# PCB-DISP128x32.net
KiCad netlist of a schematic drawn in EAGLE
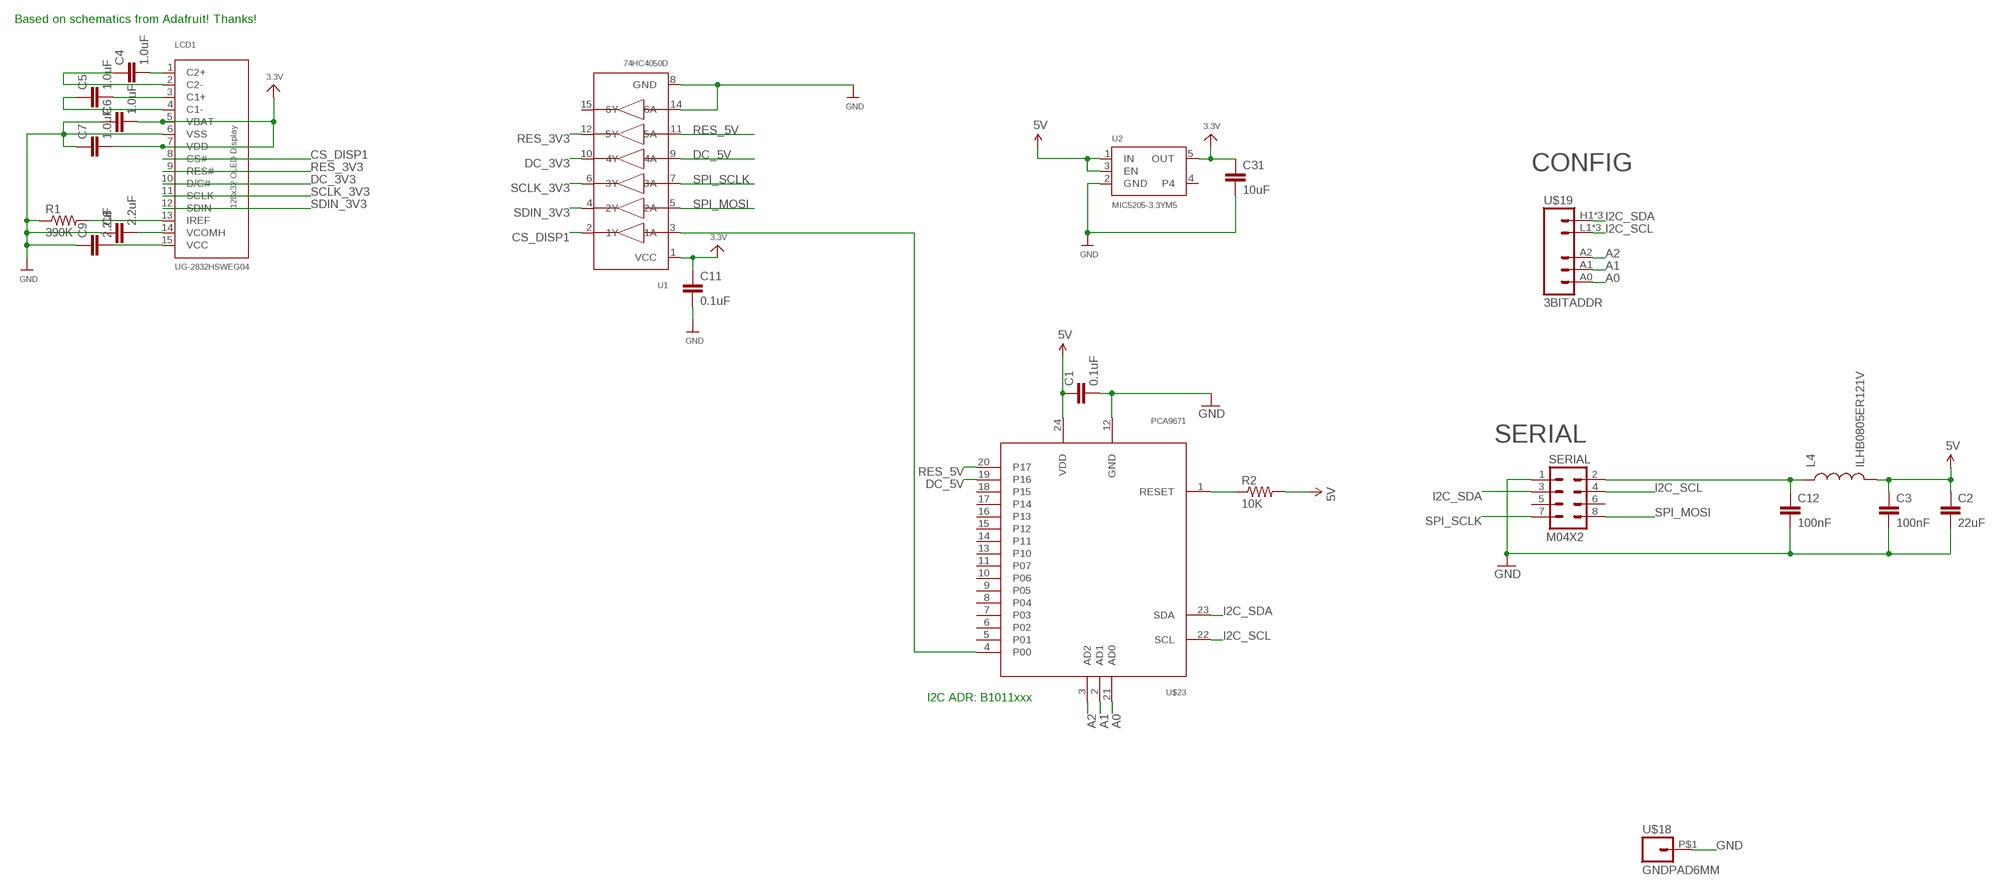
[diagram p0: schematic, sheet 1]

(export (version "E")
  (design (tool "Eeschema 10.0.6"))
  (components
    (comp (ref "C1")
      (value "0.1uF")
      (footprint "eagle-import:0603-CAP")
      (libsource (lib "eagle-import") (part "CAP0603-CAP"))
    )
    (comp (ref "C2")
      (value "22uF")
      (footprint "eagle-import:0805")
      (libsource (lib "eagle-import") (part "CAP0805"))
    )
    (comp (ref "C3")
      (value "100nF")
      (footprint "eagle-import:0603-CAP")
      (libsource (lib "eagle-import") (part "CAP0603-CAP"))
    )
    (comp (ref "C4")
      (value "1.0uF")
      (footprint "eagle-import:0603-CAP")
      (libsource (lib "eagle-import") (part "CAP0603-CAP"))
    )
    (comp (ref "C5")
      (value "1.0uF")
      (footprint "eagle-import:0603-CAP")
      (libsource (lib "eagle-import") (part "CAP0603-CAP"))
    )
    (comp (ref "C6")
      (value "1.0uF")
      (footprint "eagle-import:0603-CAP")
      (libsource (lib "eagle-import") (part "CAP0603-CAP"))
    )
    (comp (ref "C7")
      (value "1.0uF")
      (footprint "eagle-import:0603-CAP")
      (libsource (lib "eagle-import") (part "CAP0603-CAP"))
    )
    (comp (ref "C8")
      (value "2.2uF")
      (footprint "eagle-import:0603-CAP")
      (libsource (lib "eagle-import") (part "CAP0603-CAP"))
    )
    (comp (ref "C9")
      (value "2.2uF")
      (footprint "eagle-import:0603-CAP")
      (libsource (lib "eagle-import") (part "CAP0603-CAP"))
    )
    (comp (ref "C11")
      (value "0.1uF")
      (footprint "eagle-import:0603-CAP")
      (libsource (lib "eagle-import") (part "CAP0603-CAP"))
    )
    (comp (ref "C12")
      (value "100nF")
      (footprint "eagle-import:0603-CAP")
      (libsource (lib "eagle-import") (part "CAP0603-CAP"))
    )
    (comp (ref "C31")
      (value "10uF")
      (footprint "eagle-import:0805")
      (libsource (lib "eagle-import") (part "CAP0805"))
    )
    (comp (ref "L4")
      (value "ILHB0805ER121V")
      (footprint "eagle-import:0805")
      (libsource (lib "eagle-import") (part "INDUCTOR0805"))
    )
    (comp (ref "LCD1")
      (value "UG-2832HSWEG04")
      (footprint "eagle-import:UG-2832HSWEG04_WRAPAROUND")
      (libsource (lib "eagle-import") (part "OLED_UG-2832HSWEG04WRAPAROUND"))
    )
    (comp (ref "R1")
      (value "390K")
      (footprint "eagle-import:0603-RES")
      (libsource (lib "eagle-import") (part "RESISTOR0603-RES"))
    )
    (comp (ref "R2")
      (value "10K")
      (footprint "eagle-import:0603-RES")
      (libsource (lib "eagle-import") (part "RESISTOR0603-RES"))
    )
    (comp (ref "SERIAL")
      (value "M04X2")
      (footprint "eagle-import:2X4")
      (libsource (lib "eagle-import") (part "M04X2"))
    )
    (comp (ref "U$18")
      (value "GNDPAD6MM")
      (footprint "eagle-import:3.2MMPAD6MM")
      (libsource (lib "eagle-import") (part "GNDPAD6MM"))
    )
    (comp (ref "U$19")
      (value "3BITADDR")
      (footprint "eagle-import:3BITADDR")
      (libsource (lib "eagle-import") (part "3BITADDR"))
    )
    (comp (ref "U$23")
      (value "PCA9671")
      (footprint "eagle-import:TSSOP24")
      (libsource (lib "eagle-import") (part "PCA9671"))
    )
    (comp (ref "U1")
      (value "74HC4050D")
      (footprint "eagle-import:TSSOP16")
      (libsource (lib "eagle-import") (part "74HC4050DTSSOP16"))
    )
    (comp (ref "U2")
      (value "MIC5205-3.3YM5")
      (footprint "eagle-import:SOT23-5")
      (libsource (lib "eagle-import") (part "VREG_SOT23-5"))
    )
  )
  (nets
    (net (code "1") (name "3.3V") (class "Default")
      (node (ref "C11") (pin "1") (pinfunction "1_1") (pintype "passive"))
      (node (ref "C31") (pin "1") (pinfunction "1_1") (pintype "passive"))
      (node (ref "C6") (pin "2") (pinfunction "2_2") (pintype "passive"))
      (node (ref "C7") (pin "2") (pinfunction "2_2") (pintype "passive"))
      (node (ref "LCD1") (pin "5") (pinfunction "VBAT_5") (pintype "bidirectional"))
      (node (ref "LCD1") (pin "7") (pinfunction "VDD_7") (pintype "bidirectional"))
      (node (ref "U1") (pin "1") (pinfunction "VCC_1") (pintype "bidirectional"))
      (node (ref "U2") (pin "5") (pinfunction "OUT_5") (pintype "bidirectional"))
    )
    (net (code "2") (name "5V") (class "Default")
      (node (ref "C1") (pin "1") (pinfunction "1_1") (pintype "passive"))
      (node (ref "C2") (pin "1") (pinfunction "1_1") (pintype "passive"))
      (node (ref "C3") (pin "1") (pinfunction "1_1") (pintype "passive"))
      (node (ref "L4") (pin "2") (pinfunction "2_2") (pintype "passive"))
      (node (ref "R2") (pin "2") (pinfunction "2_2") (pintype "passive"))
      (node (ref "U$23") (pin "24") (pinfunction "VDD_24") (pintype "power_in"))
      (node (ref "U2") (pin "1") (pinfunction "IN_1") (pintype "bidirectional"))
      (node (ref "U2") (pin "3") (pinfunction "EN_3") (pintype "bidirectional"))
    )
    (net (code "3") (name "A0") (class "Default")
      (node (ref "U$19") (pin "A0") (pinfunction "A0_A0") (pintype "passive"))
      (node (ref "U$23") (pin "21") (pinfunction "AD0_21") (pintype "input"))
    )
    (net (code "4") (name "A1") (class "Default")
      (node (ref "U$19") (pin "A1") (pinfunction "A1_A1") (pintype "passive"))
      (node (ref "U$23") (pin "2") (pinfunction "AD1_2") (pintype "input"))
    )
    (net (code "5") (name "A2") (class "Default")
      (node (ref "U$19") (pin "A2") (pinfunction "A2_A2") (pintype "passive"))
      (node (ref "U$23") (pin "3") (pinfunction "AD2_3") (pintype "input"))
    )
    (net (code "6") (name "CS_DISP1") (class "Default")
      (node (ref "LCD1") (pin "8") (pinfunction "CS#_8") (pintype "bidirectional"))
      (node (ref "U1") (pin "2") (pinfunction "1Y_2") (pintype "bidirectional"))
    )
    (net (code "7") (name "DC_3V3") (class "Default")
      (node (ref "LCD1") (pin "10") (pinfunction "D/C#_10") (pintype "bidirectional"))
      (node (ref "U1") (pin "10") (pinfunction "4Y_10") (pintype "bidirectional"))
    )
    (net (code "8") (name "DC_5V") (class "Default")
      (node (ref "U$23") (pin "19") (pinfunction "P16_19") (pintype "output"))
      (node (ref "U1") (pin "9") (pinfunction "4A_9") (pintype "bidirectional"))
    )
    (net (code "9") (name "GND") (class "Default")
      (node (ref "C1") (pin "2") (pinfunction "2_2") (pintype "passive"))
      (node (ref "C11") (pin "2") (pinfunction "2_2") (pintype "passive"))
      (node (ref "C12") (pin "2") (pinfunction "2_2") (pintype "passive"))
      (node (ref "C2") (pin "2") (pinfunction "2_2") (pintype "passive"))
      (node (ref "C3") (pin "2") (pinfunction "2_2") (pintype "passive"))
      (node (ref "C31") (pin "2") (pinfunction "2_2") (pintype "passive"))
      (node (ref "C6") (pin "1") (pinfunction "1_1") (pintype "passive"))
      (node (ref "C7") (pin "1") (pinfunction "1_1") (pintype "passive"))
      (node (ref "C8") (pin "1") (pinfunction "1_1") (pintype "passive"))
      (node (ref "C9") (pin "1") (pinfunction "1_1") (pintype "passive"))
      (node (ref "LCD1") (pin "6") (pinfunction "VSS_6") (pintype "bidirectional"))
      (node (ref "R1") (pin "1") (pinfunction "1_1") (pintype "passive"))
      (node (ref "SERIAL") (pin "1") (pinfunction "1_1") (pintype "passive"))
      (node (ref "U$18") (pin "P$1") (pinfunction "1_P$1") (pintype "passive"))
      (node (ref "U$23") (pin "12") (pinfunction "GND_12") (pintype "power_in"))
      (node (ref "U1") (pin "14") (pinfunction "6A_14") (pintype "bidirectional"))
      (node (ref "U1") (pin "8") (pinfunction "GND_8") (pintype "bidirectional"))
      (node (ref "U2") (pin "2") (pinfunction "GND_2") (pintype "bidirectional"))
    )
    (net (code "10") (name "I2C_SCL") (class "Default")
      (node (ref "SERIAL") (pin "4") (pinfunction "4_4") (pintype "passive"))
      (node (ref "U$19") (pin "L1") (pinfunction "GND_L1") (pintype "passive"))
      (node (ref "U$19") (pin "L2") (pinfunction "GND_L2") (pintype "passive"))
      (node (ref "U$19") (pin "L3") (pinfunction "GND_L3") (pintype "passive"))
      (node (ref "U$23") (pin "22") (pinfunction "SCL_22") (pintype "input"))
    )
    (net (code "11") (name "I2C_SDA") (class "Default")
      (node (ref "SERIAL") (pin "3") (pinfunction "3_3") (pintype "passive"))
      (node (ref "U$19") (pin "H1") (pinfunction "VCC_H1") (pintype "passive"))
      (node (ref "U$19") (pin "H2") (pinfunction "VCC_H2") (pintype "passive"))
      (node (ref "U$19") (pin "H3") (pinfunction "VCC_H3") (pintype "passive"))
      (node (ref "U$23") (pin "23") (pinfunction "SDA_23") (pintype "input"))
    )
    (net (code "12") (name "Net-(C12-Pad1)") (class "Default")
      (node (ref "C12") (pin "1") (pinfunction "1_1") (pintype "passive"))
      (node (ref "L4") (pin "1") (pinfunction "1_1") (pintype "passive"))
      (node (ref "SERIAL") (pin "2") (pinfunction "2_2") (pintype "passive"))
    )
    (net (code "13") (name "Net-(LCD1-C1+)") (class "Default")
      (node (ref "C5") (pin "2") (pinfunction "2_2") (pintype "passive"))
      (node (ref "LCD1") (pin "3") (pinfunction "C1+_3") (pintype "bidirectional"))
    )
    (net (code "14") (name "Net-(LCD1-C1-)") (class "Default")
      (node (ref "C5") (pin "1") (pinfunction "1_1") (pintype "passive"))
      (node (ref "LCD1") (pin "4") (pinfunction "C1-_4") (pintype "bidirectional"))
    )
    (net (code "15") (name "Net-(LCD1-C2+)") (class "Default")
      (node (ref "C4") (pin "2") (pinfunction "2_2") (pintype "passive"))
      (node (ref "LCD1") (pin "1") (pinfunction "C2+_1") (pintype "bidirectional"))
    )
    (net (code "16") (name "Net-(LCD1-C2-)") (class "Default")
      (node (ref "C4") (pin "1") (pinfunction "1_1") (pintype "passive"))
      (node (ref "LCD1") (pin "2") (pinfunction "C2-_2") (pintype "bidirectional"))
    )
    (net (code "17") (name "Net-(LCD1-IREF)") (class "Default")
      (node (ref "LCD1") (pin "13") (pinfunction "IREF_13") (pintype "bidirectional"))
      (node (ref "R1") (pin "2") (pinfunction "2_2") (pintype "passive"))
    )
    (net (code "18") (name "Net-(LCD1-VCC)") (class "Default")
      (node (ref "C9") (pin "2") (pinfunction "2_2") (pintype "passive"))
      (node (ref "LCD1") (pin "15") (pinfunction "VCC_15") (pintype "bidirectional"))
    )
    (net (code "19") (name "Net-(LCD1-VCOMH)") (class "Default")
      (node (ref "C8") (pin "2") (pinfunction "2_2") (pintype "passive"))
      (node (ref "LCD1") (pin "14") (pinfunction "VCOMH_14") (pintype "bidirectional"))
    )
    (net (code "20") (name "Net-(U$23-P00)") (class "Default")
      (node (ref "U$23") (pin "4") (pinfunction "P00_4") (pintype "output"))
      (node (ref "U1") (pin "3") (pinfunction "1A_3") (pintype "bidirectional"))
    )
    (net (code "21") (name "Net-(U$23-RESET)") (class "Default")
      (node (ref "R2") (pin "1") (pinfunction "1_1") (pintype "passive"))
      (node (ref "U$23") (pin "1") (pinfunction "RESET_1") (pintype "input"))
    )
    (net (code "22") (name "RES_3V3") (class "Default")
      (node (ref "LCD1") (pin "9") (pinfunction "RES#_9") (pintype "bidirectional"))
      (node (ref "U1") (pin "12") (pinfunction "5Y_12") (pintype "bidirectional"))
    )
    (net (code "23") (name "RES_5V") (class "Default")
      (node (ref "U$23") (pin "20") (pinfunction "P17_20") (pintype "output"))
      (node (ref "U1") (pin "11") (pinfunction "5A_11") (pintype "bidirectional"))
    )
    (net (code "24") (name "SCLK_3V3") (class "Default")
      (node (ref "LCD1") (pin "11") (pinfunction "SCLK_11") (pintype "bidirectional"))
      (node (ref "U1") (pin "6") (pinfunction "3Y_6") (pintype "bidirectional"))
    )
    (net (code "25") (name "SDIN_3V3") (class "Default")
      (node (ref "LCD1") (pin "12") (pinfunction "SDIN_12") (pintype "bidirectional"))
      (node (ref "U1") (pin "4") (pinfunction "2Y_4") (pintype "bidirectional"))
    )
    (net (code "26") (name "SPI_MOSI") (class "Default")
      (node (ref "SERIAL") (pin "8") (pinfunction "8_8") (pintype "passive"))
      (node (ref "U1") (pin "5") (pinfunction "2A_5") (pintype "bidirectional"))
    )
    (net (code "27") (name "SPI_SCLK") (class "Default")
      (node (ref "SERIAL") (pin "7") (pinfunction "7_7") (pintype "passive"))
      (node (ref "U1") (pin "7") (pinfunction "3A_7") (pintype "bidirectional"))
    )
    (net (code "28") (name "unconnected-(SERIAL-Pad5)") (class "Default")
      (node (ref "SERIAL") (pin "5") (pinfunction "5_5") (pintype "passive"))
    )
    (net (code "29") (name "unconnected-(SERIAL-Pad6)") (class "Default")
      (node (ref "SERIAL") (pin "6") (pinfunction "6_6") (pintype "passive"))
    )
    (net (code "30") (name "unconnected-(U$23-P01-Pad5)") (class "Default")
      (node (ref "U$23") (pin "5") (pinfunction "P01_5") (pintype "output"))
    )
    (net (code "31") (name "unconnected-(U$23-P02-Pad6)") (class "Default")
      (node (ref "U$23") (pin "6") (pinfunction "P02_6") (pintype "output"))
    )
    (net (code "32") (name "unconnected-(U$23-P03-Pad7)") (class "Default")
      (node (ref "U$23") (pin "7") (pinfunction "P03_7") (pintype "output"))
    )
    (net (code "33") (name "unconnected-(U$23-P04-Pad8)") (class "Default")
      (node (ref "U$23") (pin "8") (pinfunction "P04_8") (pintype "output"))
    )
    (net (code "34") (name "unconnected-(U$23-P05-Pad9)") (class "Default")
      (node (ref "U$23") (pin "9") (pinfunction "P05_9") (pintype "output"))
    )
    (net (code "35") (name "unconnected-(U$23-P06-Pad10)") (class "Default")
      (node (ref "U$23") (pin "10") (pinfunction "P06_10") (pintype "output"))
    )
    (net (code "36") (name "unconnected-(U$23-P07-Pad11)") (class "Default")
      (node (ref "U$23") (pin "11") (pinfunction "P07_11") (pintype "output"))
    )
    (net (code "37") (name "unconnected-(U$23-P10-Pad13)") (class "Default")
      (node (ref "U$23") (pin "13") (pinfunction "P10_13") (pintype "output"))
    )
    (net (code "38") (name "unconnected-(U$23-P11-Pad14)") (class "Default")
      (node (ref "U$23") (pin "14") (pinfunction "P11_14") (pintype "output"))
    )
    (net (code "39") (name "unconnected-(U$23-P12-Pad15)") (class "Default")
      (node (ref "U$23") (pin "15") (pinfunction "P12_15") (pintype "output"))
    )
    (net (code "40") (name "unconnected-(U$23-P13-Pad16)") (class "Default")
      (node (ref "U$23") (pin "16") (pinfunction "P13_16") (pintype "output"))
    )
    (net (code "41") (name "unconnected-(U$23-P14-Pad17)") (class "Default")
      (node (ref "U$23") (pin "17") (pinfunction "P14_17") (pintype "output"))
    )
    (net (code "42") (name "unconnected-(U$23-P15-Pad18)") (class "Default")
      (node (ref "U$23") (pin "18") (pinfunction "P15_18") (pintype "output"))
    )
    (net (code "43") (name "unconnected-(U1-6Y-Pad15)") (class "Default")
      (node (ref "U1") (pin "15") (pinfunction "6Y_15") (pintype "bidirectional"))
    )
    (net (code "44") (name "unconnected-(U2-P4-Pad4)") (class "Default")
      (node (ref "U2") (pin "4") (pinfunction "P4_4") (pintype "bidirectional"))
    )
  )
)
